# LBSS.net
KiCad netlist of a schematic drawn in EAGLE
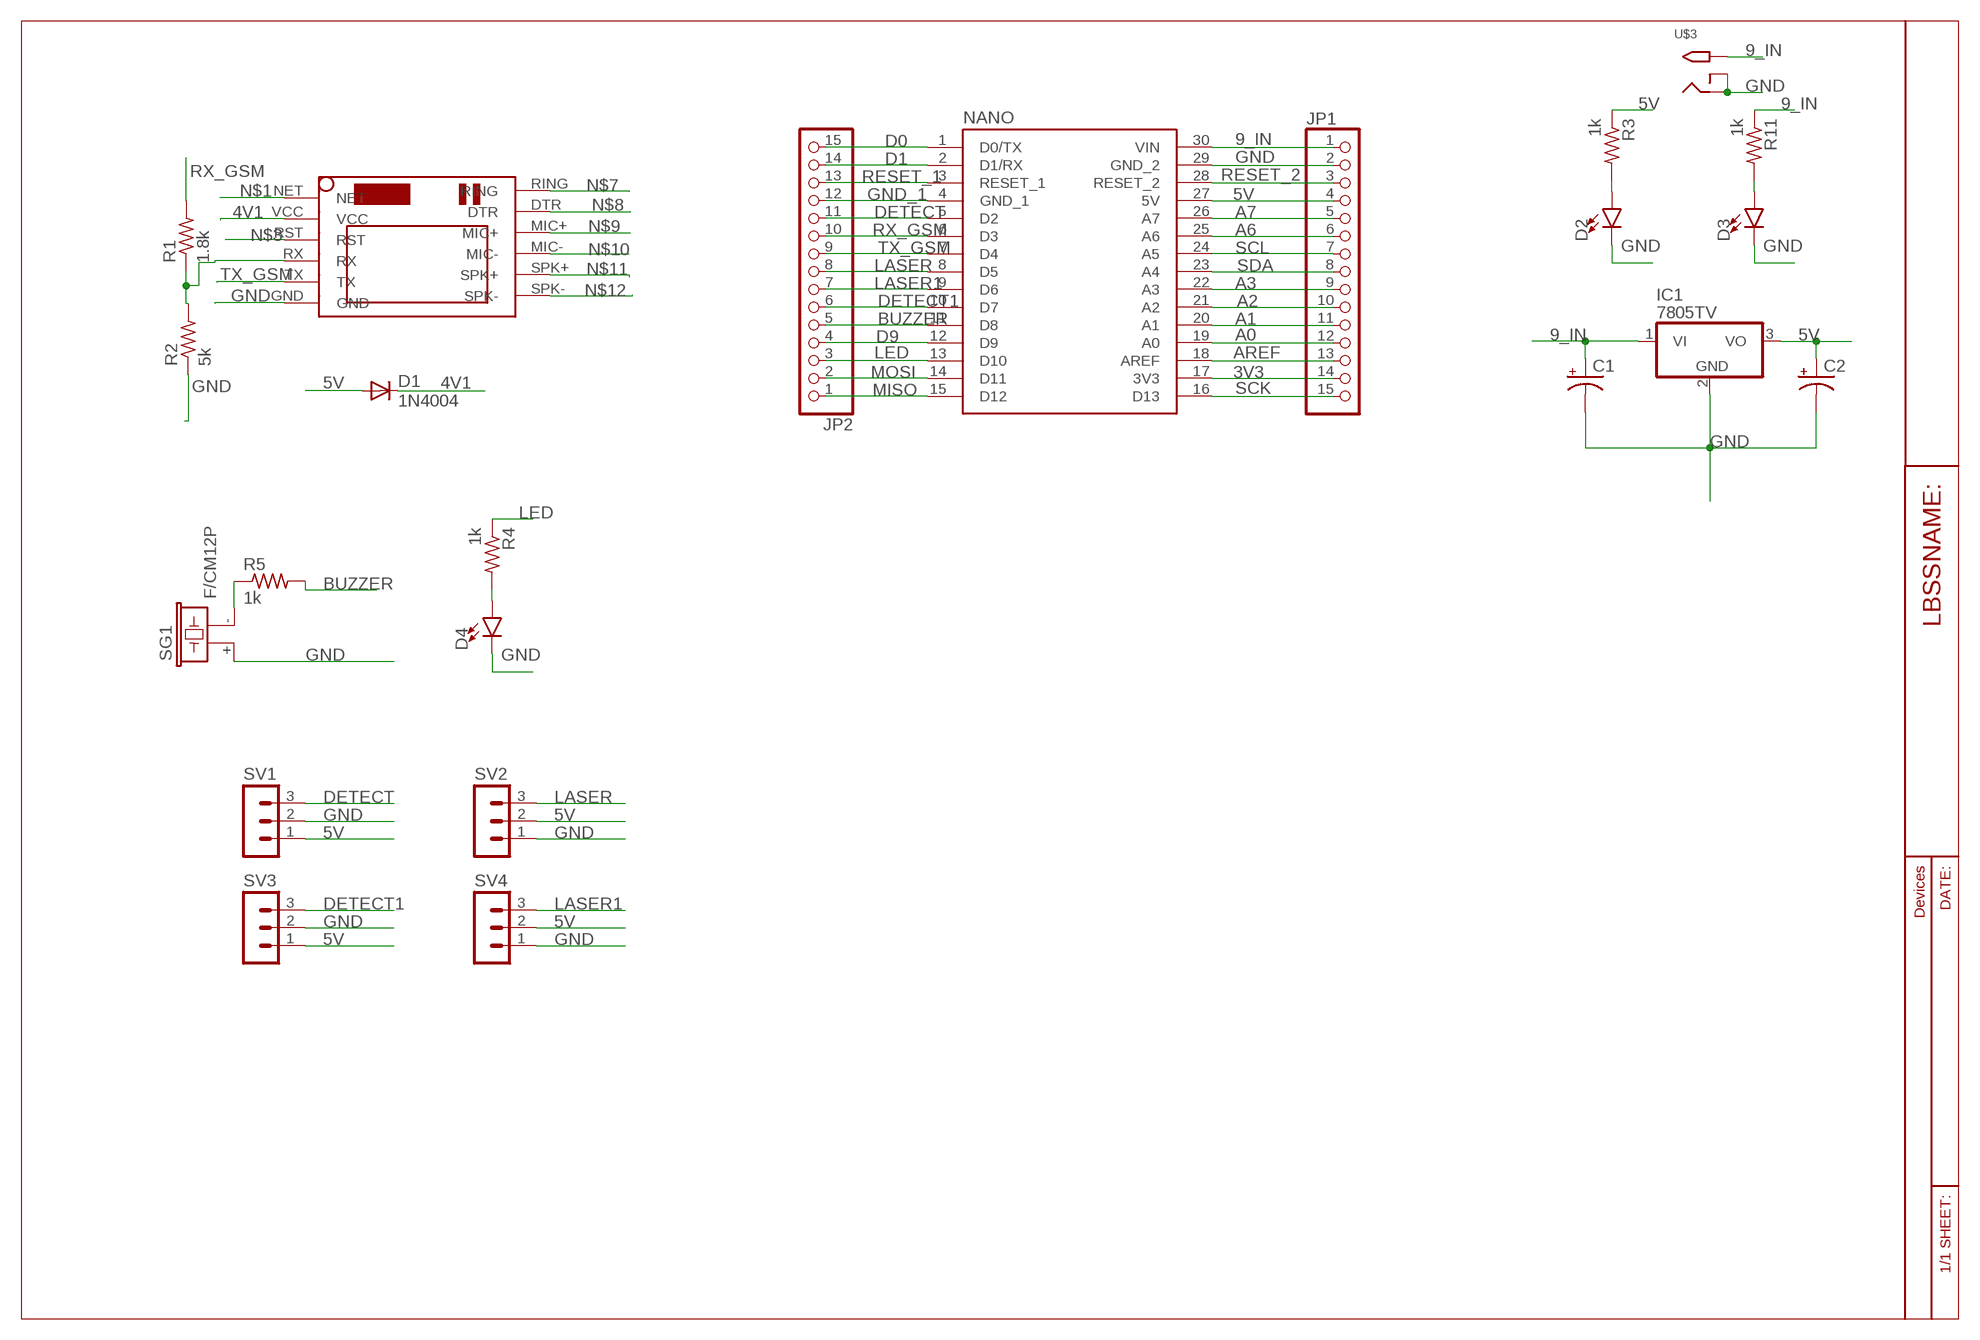
[diagram p0: schematic, sheet 1]

(export (version "E")
  (design (tool "Eeschema 10.0.6"))
  (components
    (comp (ref "C1")
      (value "CPOL-USE3.5-8")
      (footprint "eagle-import:E3,5-8")
      (libsource (lib "eagle-import") (part "CPOL-USE3.5-8"))
    )
    (comp (ref "C2")
      (value "CPOL-USE3.5-8")
      (footprint "eagle-import:E3,5-8")
      (libsource (lib "eagle-import") (part "CPOL-USE3.5-8"))
    )
    (comp (ref "D1")
      (value "1N4004")
      (footprint "eagle-import:DO41-10")
      (libsource (lib "eagle-import") (part "1N4004"))
    )
    (comp (ref "D2")
      (value "LED3MM")
      (footprint "eagle-import:LED_3MM")
      (libsource (lib "eagle-import") (part "LED3MM"))
    )
    (comp (ref "D3")
      (value "LED3MM")
      (footprint "eagle-import:LED_3MM")
      (libsource (lib "eagle-import") (part "LED3MM"))
    )
    (comp (ref "D4")
      (value "LED3MM")
      (footprint "eagle-import:LED_3MM")
      (libsource (lib "eagle-import") (part "LED3MM"))
    )
    (comp (ref "IC1")
      (value "7805TV")
      (footprint "eagle-import:TO220V")
      (libsource (lib "eagle-import") (part "78TV05"))
    )
    (comp (ref "JP1")
      (value "PINHD-1X15")
      (footprint "eagle-import:1X15")
      (libsource (lib "eagle-import") (part "PINHD-1X15"))
    )
    (comp (ref "JP2")
      (value "PINHD-1X15")
      (footprint "eagle-import:1X15")
      (libsource (lib "eagle-import") (part "PINHD-1X15"))
    )
    (comp (ref "NANO")
      (value "A000005")
      (footprint "eagle-import:MODULE_A000005")
      (fields (field (name "MF") "Arduino"))
      (libsource (lib "eagle-import") (part "A000005"))
    )
    (comp (ref "R1")
      (value "1.8k")
      (footprint "eagle-import:0207_10")
      (libsource (lib "eagle-import") (part "rcl_334_R-US_0207/10"))
    )
    (comp (ref "R2")
      (value "5k")
      (footprint "eagle-import:0207_10")
      (libsource (lib "eagle-import") (part "rcl_334_R-US_0207/10"))
    )
    (comp (ref "R3")
      (value "1k")
      (footprint "eagle-import:M0805")
      (libsource (lib "eagle-import") (part "R-US_M0805"))
    )
    (comp (ref "R4")
      (value "1k")
      (footprint "eagle-import:M0805")
      (libsource (lib "eagle-import") (part "R-US_M0805"))
    )
    (comp (ref "R5")
      (value "1k")
      (footprint "eagle-import:M0805")
      (libsource (lib "eagle-import") (part "R-US_M0805"))
    )
    (comp (ref "R11")
      (value "1k")
      (footprint "eagle-import:M0805")
      (libsource (lib "eagle-import") (part "R-US_M0805"))
    )
    (comp (ref "SG1")
      (value "F/CM12P")
      (footprint "eagle-import:F_CM12P")
      (libsource (lib "eagle-import") (part "F/CM12P"))
    )
    (comp (ref "SV1")
      (value "MA03-1")
      (footprint "eagle-import:MA03-1")
      (libsource (lib "eagle-import") (part "MA03-1"))
    )
    (comp (ref "SV2")
      (value "MA03-1")
      (footprint "eagle-import:MA03-1")
      (libsource (lib "eagle-import") (part "MA03-1"))
    )
    (comp (ref "SV3")
      (value "MA03-1")
      (footprint "eagle-import:MA03-1")
      (libsource (lib "eagle-import") (part "MA03-1"))
    )
    (comp (ref "SV4")
      (value "MA03-1")
      (footprint "eagle-import:MA03-1")
      (libsource (lib "eagle-import") (part "MA03-1"))
    )
    (comp (ref "U$1")
      (value "SIM800LMODULE")
      (footprint "eagle-import:SIM800LMODULE")
      (libsource (lib "eagle-import") (part "SIM800LMODULE"))
    )
    (comp (ref "U$3")
      (value "2.1MMJACKTHM")
      (footprint "eagle-import:PJ-102A")
      (libsource (lib "eagle-import") (part "2.1MMJACKTHM"))
    )
  )
  (nets
    (net (code "1") (name "/3V3") (class "Default")
      (node (ref "JP1") (pin "14") (pinfunction "14_14") (pintype "passive"))
      (node (ref "NANO") (pin "17") (pinfunction "3V3_17") (pintype "power_in"))
    )
    (net (code "2") (name "/4V1") (class "Default")
      (node (ref "D1") (pin "C") (pinfunction "C_C") (pintype "passive"))
      (node (ref "U$1") (pin "VCC") (pinfunction "VCC_VCC") (pintype "bidirectional"))
    )
    (net (code "3") (name "/5V") (class "Default")
      (node (ref "C2") (pin "+") (pinfunction "+_+") (pintype "passive"))
      (node (ref "D1") (pin "A") (pinfunction "A_A") (pintype "passive"))
      (node (ref "IC1") (pin "3") (pinfunction "VO_3") (pintype "passive"))
      (node (ref "JP1") (pin "4") (pinfunction "4_4") (pintype "passive"))
      (node (ref "NANO") (pin "27") (pinfunction "5V_27") (pintype "power_in"))
      (node (ref "R3") (pin "1") (pinfunction "1_1") (pintype "passive"))
      (node (ref "SV1") (pin "1") (pinfunction "1_1") (pintype "passive"))
      (node (ref "SV2") (pin "2") (pinfunction "2_2") (pintype "passive"))
      (node (ref "SV3") (pin "1") (pinfunction "1_1") (pintype "passive"))
      (node (ref "SV4") (pin "2") (pinfunction "2_2") (pintype "passive"))
    )
    (net (code "4") (name "/9_IN") (class "Default")
      (node (ref "C1") (pin "+") (pinfunction "+_+") (pintype "passive"))
      (node (ref "IC1") (pin "1") (pinfunction "VI_1") (pintype "input"))
      (node (ref "JP1") (pin "1") (pinfunction "1_1") (pintype "passive"))
      (node (ref "NANO") (pin "30") (pinfunction "VIN_30") (pintype "power_in"))
      (node (ref "R11") (pin "1") (pinfunction "1_1") (pintype "passive"))
      (node (ref "U$3") (pin "TIP") (pinfunction "TIP_TIP") (pintype "bidirectional"))
    )
    (net (code "5") (name "/A0") (class "Default")
      (node (ref "JP1") (pin "12") (pinfunction "12_12") (pintype "passive"))
      (node (ref "NANO") (pin "19") (pinfunction "A0_19") (pintype "input"))
    )
    (net (code "6") (name "/A1") (class "Default")
      (node (ref "JP1") (pin "11") (pinfunction "11_11") (pintype "passive"))
      (node (ref "NANO") (pin "20") (pinfunction "A1_20") (pintype "input"))
    )
    (net (code "7") (name "/A2") (class "Default")
      (node (ref "JP1") (pin "10") (pinfunction "10_10") (pintype "passive"))
      (node (ref "NANO") (pin "21") (pinfunction "A2_21") (pintype "input"))
    )
    (net (code "8") (name "/A3") (class "Default")
      (node (ref "JP1") (pin "9") (pinfunction "9_9") (pintype "passive"))
      (node (ref "NANO") (pin "22") (pinfunction "A3_22") (pintype "input"))
    )
    (net (code "9") (name "/A6") (class "Default")
      (node (ref "JP1") (pin "6") (pinfunction "6_6") (pintype "passive"))
      (node (ref "NANO") (pin "25") (pinfunction "A6_25") (pintype "input"))
    )
    (net (code "10") (name "/A7") (class "Default")
      (node (ref "JP1") (pin "5") (pinfunction "5_5") (pintype "passive"))
      (node (ref "NANO") (pin "26") (pinfunction "A7_26") (pintype "input"))
    )
    (net (code "11") (name "/AREF") (class "Default")
      (node (ref "JP1") (pin "13") (pinfunction "13_13") (pintype "passive"))
      (node (ref "NANO") (pin "18") (pinfunction "AREF_18") (pintype "input"))
    )
    (net (code "12") (name "/BUZZER") (class "Default")
      (node (ref "JP2") (pin "5") (pinfunction "5_5") (pintype "passive"))
      (node (ref "NANO") (pin "11") (pinfunction "D8_11") (pintype "bidirectional"))
      (node (ref "R5") (pin "2") (pinfunction "2_2") (pintype "passive"))
    )
    (net (code "13") (name "/D0") (class "Default")
      (node (ref "JP2") (pin "15") (pinfunction "15_15") (pintype "passive"))
      (node (ref "NANO") (pin "1") (pinfunction "D0/TX_1") (pintype "bidirectional"))
    )
    (net (code "14") (name "/D1") (class "Default")
      (node (ref "JP2") (pin "14") (pinfunction "14_14") (pintype "passive"))
      (node (ref "NANO") (pin "2") (pinfunction "D1/RX_2") (pintype "bidirectional"))
    )
    (net (code "15") (name "/D9") (class "Default")
      (node (ref "JP2") (pin "4") (pinfunction "4_4") (pintype "passive"))
      (node (ref "NANO") (pin "12") (pinfunction "D9_12") (pintype "bidirectional"))
    )
    (net (code "16") (name "/DETECT") (class "Default")
      (node (ref "JP2") (pin "11") (pinfunction "11_11") (pintype "passive"))
      (node (ref "NANO") (pin "5") (pinfunction "D2_5") (pintype "bidirectional"))
      (node (ref "SV1") (pin "3") (pinfunction "3_3") (pintype "passive"))
    )
    (net (code "17") (name "/DETECT1") (class "Default")
      (node (ref "JP2") (pin "6") (pinfunction "6_6") (pintype "passive"))
      (node (ref "NANO") (pin "10") (pinfunction "D7_10") (pintype "bidirectional"))
      (node (ref "SV3") (pin "3") (pinfunction "3_3") (pintype "passive"))
    )
    (net (code "18") (name "/GND") (class "Default")
      (node (ref "C1") (pin "-") (pinfunction "-_-") (pintype "passive"))
      (node (ref "C2") (pin "-") (pinfunction "-_-") (pintype "passive"))
      (node (ref "D2") (pin "K") (pinfunction "C_K") (pintype "passive"))
      (node (ref "D3") (pin "K") (pinfunction "C_K") (pintype "passive"))
      (node (ref "D4") (pin "K") (pinfunction "C_K") (pintype "passive"))
      (node (ref "IC1") (pin "2") (pinfunction "GND_2") (pintype "passive"))
      (node (ref "JP1") (pin "2") (pinfunction "2_2") (pintype "passive"))
      (node (ref "NANO") (pin "29") (pinfunction "GND_2_29") (pintype "power_in"))
      (node (ref "R2") (pin "1") (pinfunction "1_1") (pintype "passive"))
      (node (ref "SG1") (pin "+") (pinfunction "1_+") (pintype "passive"))
      (node (ref "SV1") (pin "2") (pinfunction "2_2") (pintype "passive"))
      (node (ref "SV2") (pin "1") (pinfunction "1_1") (pintype "passive"))
      (node (ref "SV3") (pin "2") (pinfunction "2_2") (pintype "passive"))
      (node (ref "SV4") (pin "1") (pinfunction "1_1") (pintype "passive"))
      (node (ref "U$1") (pin "GND") (pinfunction "GND_GND") (pintype "bidirectional"))
      (node (ref "U$3") (pin "RING") (pinfunction "RING_RING") (pintype "bidirectional"))
      (node (ref "U$3") (pin "RING_SW") (pinfunction "RING_SW_RING_SW") (pintype "bidirectional"))
    )
    (net (code "19") (name "/GND_1") (class "Default")
      (node (ref "JP2") (pin "12") (pinfunction "12_12") (pintype "passive"))
      (node (ref "NANO") (pin "4") (pinfunction "GND_1_4") (pintype "power_in"))
    )
    (net (code "20") (name "/LASER") (class "Default")
      (node (ref "JP2") (pin "8") (pinfunction "8_8") (pintype "passive"))
      (node (ref "NANO") (pin "8") (pinfunction "D5_8") (pintype "bidirectional"))
      (node (ref "SV2") (pin "3") (pinfunction "3_3") (pintype "passive"))
    )
    (net (code "21") (name "/LASER1") (class "Default")
      (node (ref "JP2") (pin "7") (pinfunction "7_7") (pintype "passive"))
      (node (ref "NANO") (pin "9") (pinfunction "D6_9") (pintype "bidirectional"))
      (node (ref "SV4") (pin "3") (pinfunction "3_3") (pintype "passive"))
    )
    (net (code "22") (name "/LED") (class "Default")
      (node (ref "JP2") (pin "3") (pinfunction "3_3") (pintype "passive"))
      (node (ref "NANO") (pin "13") (pinfunction "D10_13") (pintype "bidirectional"))
      (node (ref "R4") (pin "1") (pinfunction "1_1") (pintype "passive"))
    )
    (net (code "23") (name "/MISO") (class "Default")
      (node (ref "JP2") (pin "1") (pinfunction "1_1") (pintype "passive"))
      (node (ref "NANO") (pin "15") (pinfunction "D12_15") (pintype "bidirectional"))
    )
    (net (code "24") (name "/MOSI") (class "Default")
      (node (ref "JP2") (pin "2") (pinfunction "2_2") (pintype "passive"))
      (node (ref "NANO") (pin "14") (pinfunction "D11_14") (pintype "bidirectional"))
    )
    (net (code "25") (name "/N$1") (class "Default")
      (node (ref "U$1") (pin "NET") (pinfunction "NET_NET") (pintype "bidirectional"))
    )
    (net (code "26") (name "/N$3") (class "Default")
      (node (ref "U$1") (pin "RST") (pinfunction "RST_RST") (pintype "bidirectional"))
    )
    (net (code "27") (name "/N$7") (class "Default")
      (node (ref "U$1") (pin "RING") (pinfunction "RING_RING") (pintype "bidirectional"))
    )
    (net (code "28") (name "/N$8") (class "Default")
      (node (ref "U$1") (pin "DTR") (pinfunction "DTR_DTR") (pintype "bidirectional"))
    )
    (net (code "29") (name "/N$9") (class "Default")
      (node (ref "U$1") (pin "MIC+") (pinfunction "MIC+_MIC+") (pintype "bidirectional"))
    )
    (net (code "30") (name "/N$10") (class "Default")
      (node (ref "U$1") (pin "MIC-") (pinfunction "MIC-_MIC-") (pintype "bidirectional"))
    )
    (net (code "31") (name "/N$11") (class "Default")
      (node (ref "U$1") (pin "SPK+") (pinfunction "SPK+_SPK+") (pintype "bidirectional"))
    )
    (net (code "32") (name "/N$12") (class "Default")
      (node (ref "U$1") (pin "SPK-") (pinfunction "SPK-_SPK-") (pintype "bidirectional"))
    )
    (net (code "33") (name "/RESET_1") (class "Default")
      (node (ref "JP2") (pin "13") (pinfunction "13_13") (pintype "passive"))
      (node (ref "NANO") (pin "3") (pinfunction "RESET_1_3") (pintype "input"))
    )
    (net (code "34") (name "/RESET_2") (class "Default")
      (node (ref "JP1") (pin "3") (pinfunction "3_3") (pintype "passive"))
      (node (ref "NANO") (pin "28") (pinfunction "RESET_2_28") (pintype "input"))
    )
    (net (code "35") (name "/RX_GSM") (class "Default")
      (node (ref "JP2") (pin "10") (pinfunction "10_10") (pintype "passive"))
      (node (ref "NANO") (pin "6") (pinfunction "D3_6") (pintype "bidirectional"))
      (node (ref "R1") (pin "2") (pinfunction "2_2") (pintype "passive"))
    )
    (net (code "36") (name "/SCK") (class "Default")
      (node (ref "JP1") (pin "15") (pinfunction "15_15") (pintype "passive"))
      (node (ref "NANO") (pin "16") (pinfunction "D13_16") (pintype "bidirectional"))
    )
    (net (code "37") (name "/SCL") (class "Default")
      (node (ref "JP1") (pin "7") (pinfunction "7_7") (pintype "passive"))
      (node (ref "NANO") (pin "24") (pinfunction "A5_24") (pintype "input"))
    )
    (net (code "38") (name "/SDA") (class "Default")
      (node (ref "JP1") (pin "8") (pinfunction "8_8") (pintype "passive"))
      (node (ref "NANO") (pin "23") (pinfunction "A4_23") (pintype "input"))
    )
    (net (code "39") (name "/TX_GSM") (class "Default")
      (node (ref "JP2") (pin "9") (pinfunction "9_9") (pintype "passive"))
      (node (ref "NANO") (pin "7") (pinfunction "D4_7") (pintype "bidirectional"))
      (node (ref "U$1") (pin "TX") (pinfunction "TX_TX") (pintype "bidirectional"))
    )
    (net (code "40") (name "Net-(D2-PadA)") (class "Default")
      (node (ref "D2") (pin "A") (pinfunction "A_A") (pintype "passive"))
      (node (ref "R3") (pin "2") (pinfunction "2_2") (pintype "passive"))
    )
    (net (code "41") (name "Net-(D3-PadA)") (class "Default")
      (node (ref "D3") (pin "A") (pinfunction "A_A") (pintype "passive"))
      (node (ref "R11") (pin "2") (pinfunction "2_2") (pintype "passive"))
    )
    (net (code "42") (name "Net-(D4-PadA)") (class "Default")
      (node (ref "D4") (pin "A") (pinfunction "A_A") (pintype "passive"))
      (node (ref "R4") (pin "2") (pinfunction "2_2") (pintype "passive"))
    )
    (net (code "43") (name "Net-(R1-Pad1)") (class "Default")
      (node (ref "R1") (pin "1") (pinfunction "1_1") (pintype "passive"))
      (node (ref "R2") (pin "2") (pinfunction "2_2") (pintype "passive"))
      (node (ref "U$1") (pin "RX") (pinfunction "RX_RX") (pintype "bidirectional"))
    )
    (net (code "44") (name "Net-(SG1-2)") (class "Default")
      (node (ref "R5") (pin "1") (pinfunction "1_1") (pintype "passive"))
      (node (ref "SG1") (pin "-") (pinfunction "2_-") (pintype "passive"))
    )
  )
)
